# MCU.net
KiCad netlist of a schematic drawn in Altium Designer
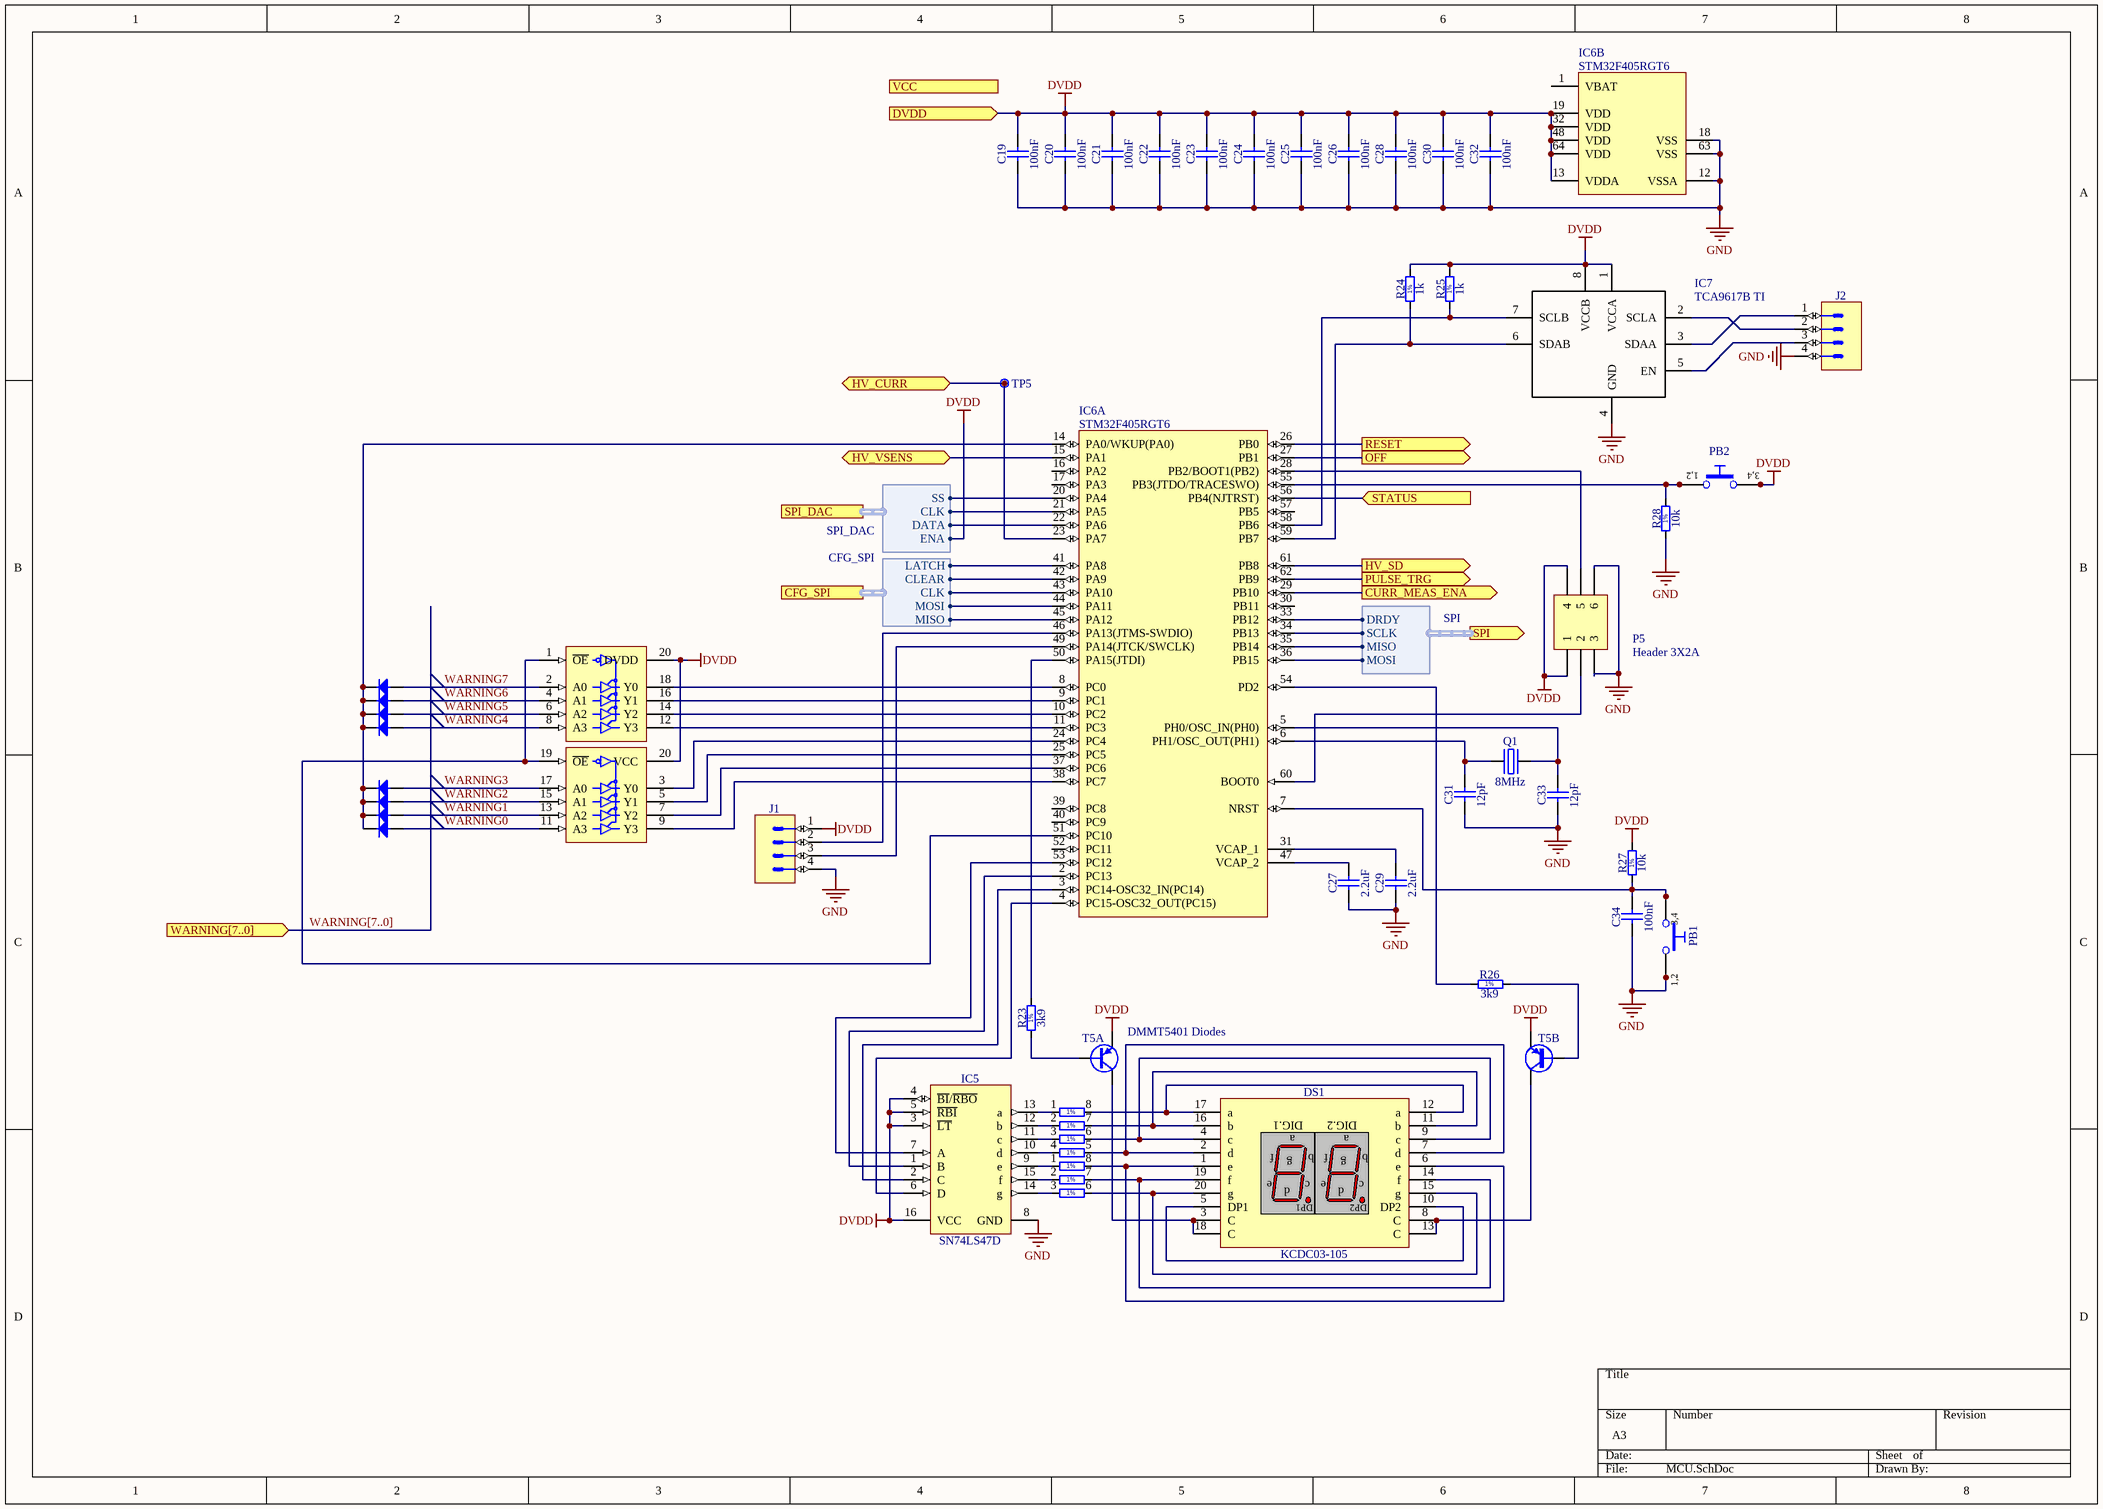
[diagram p0: MCU.SchDoc]

(export (version "E")
  (design (tool "Eeschema 10.0.6"))
  (components
    (comp (ref "C19")
      (value "100nF")
      (footprint "CAPC2012X135N")
      (description "Non-polarised capacitor")
      (fields
        (field (name "PART NUMBER") "CC0805_100NF_50V_10%_X7R")
        (field (name "VOLTAGE") "50V")
        (field (name "AUTHOR") "CERN DEM JLC")
      )
      (libsource (lib "Capacitors") (part "Capacitor - non polarized"))
    )
    (comp (ref "C20")
      (value "100nF")
      (footprint "CAPC2012X135N")
      (description "Non-polarised capacitor")
      (fields
        (field (name "PART NUMBER") "CC0805_100NF_50V_10%_X7R")
        (field (name "VOLTAGE") "50V")
        (field (name "AUTHOR") "CERN DEM JLC")
      )
      (libsource (lib "Capacitors") (part "Capacitor - non polarized"))
    )
    (comp (ref "C21")
      (value "100nF")
      (footprint "CAPC2012X135N")
      (description "Non-polarised capacitor")
      (fields
        (field (name "PART NUMBER") "CC0805_100NF_50V_10%_X7R")
        (field (name "VOLTAGE") "50V")
        (field (name "AUTHOR") "CERN DEM JLC")
      )
      (libsource (lib "Capacitors") (part "Capacitor - non polarized"))
    )
    (comp (ref "C22")
      (value "100nF")
      (footprint "CAPC2012X135N")
      (description "Non-polarised capacitor")
      (fields
        (field (name "PART NUMBER") "CC0805_100NF_50V_10%_X7R")
        (field (name "VOLTAGE") "50V")
        (field (name "AUTHOR") "CERN DEM JLC")
      )
      (libsource (lib "Capacitors") (part "Capacitor - non polarized"))
    )
    (comp (ref "C23")
      (value "100nF")
      (footprint "CAPC2012X135N")
      (description "Non-polarised capacitor")
      (fields
        (field (name "PART NUMBER") "CC0805_100NF_50V_10%_X7R")
        (field (name "VOLTAGE") "50V")
        (field (name "AUTHOR") "CERN DEM JLC")
      )
      (libsource (lib "Capacitors") (part "Capacitor - non polarized"))
    )
    (comp (ref "C24")
      (value "100nF")
      (footprint "CAPC2012X135N")
      (description "Non-polarised capacitor")
      (fields
        (field (name "PART NUMBER") "CC0805_100NF_50V_10%_X7R")
        (field (name "VOLTAGE") "50V")
        (field (name "AUTHOR") "CERN DEM JLC")
      )
      (libsource (lib "Capacitors") (part "Capacitor - non polarized"))
    )
    (comp (ref "C25")
      (value "100nF")
      (footprint "CAPC2012X135N")
      (description "Non-polarised capacitor")
      (fields
        (field (name "PART NUMBER") "CC0805_100NF_50V_10%_X7R")
        (field (name "VOLTAGE") "50V")
        (field (name "AUTHOR") "CERN DEM JLC")
      )
      (libsource (lib "Capacitors") (part "Capacitor - non polarized"))
    )
    (comp (ref "C26")
      (value "100nF")
      (footprint "CAPC2012X135N")
      (description "Non-polarised capacitor")
      (fields
        (field (name "PART NUMBER") "CC0805_100NF_50V_10%_X7R")
        (field (name "VOLTAGE") "50V")
        (field (name "AUTHOR") "CERN DEM JLC")
      )
      (libsource (lib "Capacitors") (part "Capacitor - non polarized"))
    )
    (comp (ref "C27")
      (value "2.2uF")
      (footprint "CAPC2012X135N")
      (description "Non-polarised capacitor")
      (fields
        (field (name "PART NUMBER") "CC0805_2.2UF_16V_10%_X7R")
        (field (name "VOLTAGE") "16V")
        (field (name "AUTHOR") "CERN DEM JLC")
      )
      (libsource (lib "Capacitors") (part "Capacitor - non polarized"))
    )
    (comp (ref "C28")
      (value "100nF")
      (footprint "CAPC2012X135N")
      (description "Non-polarised capacitor")
      (fields
        (field (name "PART NUMBER") "CC0805_100NF_50V_10%_X7R")
        (field (name "VOLTAGE") "50V")
        (field (name "AUTHOR") "CERN DEM JLC")
      )
      (libsource (lib "Capacitors") (part "Capacitor - non polarized"))
    )
    (comp (ref "C29")
      (value "2.2uF")
      (footprint "CAPC2012X135N")
      (description "Non-polarised capacitor")
      (fields
        (field (name "PART NUMBER") "CC0805_2.2UF_16V_10%_X7R")
        (field (name "VOLTAGE") "16V")
        (field (name "AUTHOR") "CERN DEM JLC")
      )
      (libsource (lib "Capacitors") (part "Capacitor - non polarized"))
    )
    (comp (ref "C30")
      (value "100nF")
      (footprint "CAPC2012X135N")
      (description "Non-polarised capacitor")
      (fields
        (field (name "PART NUMBER") "CC0805_100NF_50V_10%_X7R")
        (field (name "VOLTAGE") "50V")
        (field (name "AUTHOR") "CERN DEM JLC")
      )
      (libsource (lib "Capacitors") (part "Capacitor - non polarized"))
    )
    (comp (ref "C31")
      (value "12pF")
      (footprint "CAPC2012X135N")
      (description "Non-polarised capacitor")
      (fields
        (field (name "PART NUMBER") "CC0805_12PF_50V_5%_NP0")
        (field (name "VOLTAGE") "50V")
        (field (name "AUTHOR") "CERN DEM JLC")
      )
      (libsource (lib "Capacitors") (part "Capacitor - non polarized"))
    )
    (comp (ref "C32")
      (value "100nF")
      (footprint "CAPC2012X135N")
      (description "Non-polarised capacitor")
      (fields
        (field (name "PART NUMBER") "CC0805_100NF_50V_10%_X7R")
        (field (name "VOLTAGE") "50V")
        (field (name "AUTHOR") "CERN DEM JLC")
      )
      (libsource (lib "Capacitors") (part "Capacitor - non polarized"))
    )
    (comp (ref "C33")
      (value "12pF")
      (footprint "CAPC2012X135N")
      (description "Non-polarised capacitor")
      (fields
        (field (name "PART NUMBER") "CC0805_12PF_50V_5%_NP0")
        (field (name "VOLTAGE") "50V")
        (field (name "AUTHOR") "CERN DEM JLC")
      )
      (libsource (lib "Capacitors") (part "Capacitor - non polarized"))
    )
    (comp (ref "C34")
      (value "100nF")
      (footprint "CAPC2012X135N")
      (description "Non-polarised capacitor")
      (fields
        (field (name "PART NUMBER") "CC0805_100NF_50V_10%_X7R")
        (field (name "VOLTAGE") "50V")
        (field (name "AUTHOR") "CERN DEM JLC")
      )
      (libsource (lib "Capacitors") (part "Capacitor - non polarized"))
    )
    (comp (ref "D3")
      (value "MCL4148-TR3")
      (footprint "DIOMELF1911N")
      (description "Diode")
      (fields
        (field (name "VOLTAGE") "75V")
        (field (name "POWER") "200mA")
        (field (name "AUTHOR") "CERN DEM JLC")
      )
      (libsource (lib "ICs And Semiconductors") (part "Diode"))
    )
    (comp (ref "D4")
      (value "MCL4148-TR3")
      (footprint "DIOMELF1911N")
      (description "Diode")
      (fields
        (field (name "VOLTAGE") "75V")
        (field (name "POWER") "200mA")
        (field (name "AUTHOR") "CERN DEM JLC")
      )
      (libsource (lib "ICs And Semiconductors") (part "Diode"))
    )
    (comp (ref "D5")
      (value "MCL4148-TR3")
      (footprint "DIOMELF1911N")
      (description "Diode")
      (fields
        (field (name "VOLTAGE") "75V")
        (field (name "POWER") "200mA")
        (field (name "AUTHOR") "CERN DEM JLC")
      )
      (libsource (lib "ICs And Semiconductors") (part "Diode"))
    )
    (comp (ref "D6")
      (value "MCL4148-TR3")
      (footprint "DIOMELF1911N")
      (description "Diode")
      (fields
        (field (name "VOLTAGE") "75V")
        (field (name "POWER") "200mA")
        (field (name "AUTHOR") "CERN DEM JLC")
      )
      (libsource (lib "ICs And Semiconductors") (part "Diode"))
    )
    (comp (ref "D7")
      (value "MCL4148-TR3")
      (footprint "DIOMELF1911N")
      (description "Diode")
      (fields
        (field (name "VOLTAGE") "75V")
        (field (name "POWER") "200mA")
        (field (name "AUTHOR") "CERN DEM JLC")
      )
      (libsource (lib "ICs And Semiconductors") (part "Diode"))
    )
    (comp (ref "D8")
      (value "MCL4148-TR3")
      (footprint "DIOMELF1911N")
      (description "Diode")
      (fields
        (field (name "VOLTAGE") "75V")
        (field (name "POWER") "200mA")
        (field (name "AUTHOR") "CERN DEM JLC")
      )
      (libsource (lib "ICs And Semiconductors") (part "Diode"))
    )
    (comp (ref "D9")
      (value "MCL4148-TR3")
      (footprint "DIOMELF1911N")
      (description "Diode")
      (fields
        (field (name "VOLTAGE") "75V")
        (field (name "POWER") "200mA")
        (field (name "AUTHOR") "CERN DEM JLC")
      )
      (libsource (lib "ICs And Semiconductors") (part "Diode"))
    )
    (comp (ref "D10")
      (value "MCL4148-TR3")
      (footprint "DIOMELF1911N")
      (description "Diode")
      (fields
        (field (name "VOLTAGE") "75V")
        (field (name "POWER") "200mA")
        (field (name "AUTHOR") "CERN DEM JLC")
      )
      (libsource (lib "ICs And Semiconductors") (part "Diode"))
    )
    (comp (ref "DS1")
      (value "KCDC03-105")
      (footprint "DS_KINGBRIGHT_KCDC03-105")
      (description "Dual Digit, SMD 7-Segment Common Cathode Hyper Red Display")
      (fields
        (field (name "PART NUMBER") "DS_KINGBRIGHT_KCDC03-105")
        (field (name "MANUFACTURER") "KINGBRIGHT")
        (field (name "AUTHOR") "CERN DEM JLC")
      )
      (libsource (lib "ICs And Semiconductors") (part "DS_KINGBRIGHT_KCDC03-105"))
    )
    (comp (ref "IC4")
      (value "74HCT244D")
      (footprint "SOIC127P1032X265-20N")
      (description "Octal Buffer And Line Driver with 3-State Ouputs")
      (fields (field (name "MANUFACTURER") "NXP SEMICONDUCTORS") (field (name "AUTHOR") "CERN DEM JLC"))
      (libsource (lib "ICs And Semiconductors") (part "74244"))
    )
    (comp (ref "IC5")
      (value "SN74LS47D")
      (footprint "SOIC127P600X175-16N")
      (description "BCD-to-Seven-Segment Decoder/Driver")
      (fields (field (name "MANUFACTURER") "TEXAS INSTRUMENTS") (field (name "AUTHOR") "CERN DEM JMW"))
      (libsource (lib "ICs And Semiconductors") (part "7447"))
    )
    (comp (ref "IC6")
      (value "STM32F405RGT6")
      (footprint "QFP50P1200X1200X160-64N")
      (fields (field (name "MANUFACTURER") "ST MICROELECTRONICS") (field (name "AUTHOR") "CERN DEM JLC"))
      (libsource (lib "ICs And Semiconductors") (part "STM32F405RGT6"))
    )
    (comp (ref "IC7")
      (value "TCA9617B TI")
      (footprint "Additional:TSOP65P490X110-8N")
      (fields (field (name "MANUFACTURER") "TI"))
      (libsource (lib "Additional") (part "TCA9617B"))
    )
    (comp (ref "J1")
      (value "Header 4")
      (footprint "PRECI-DIP_350-V3-104-00-001101")
      (description "Connector 4 Male")
      (fields
        (field (name "PART NUMBER") "PRECI-DIP_350-V3-104-00-001101")
        (field (name "MANUFACTURER") "PRECI-DIP")
        (field (name "AUTHOR") "CERN DEM BC")
      )
      (libsource (lib "Connectors") (part "Connector 4 Male"))
    )
    (comp (ref "J2")
      (value "Header 4")
      (footprint "PRECI-DIP_350-V3-104-00-001101")
      (description "Connector 4 Male")
      (fields
        (field (name "PART NUMBER") "PRECI-DIP_350-V3-104-00-001101")
        (field (name "MANUFACTURER") "PRECI-DIP")
        (field (name "AUTHOR") "CERN DEM BC")
      )
      (libsource (lib "") (part "Connector 4 Male_1"))
    )
    (comp (ref "P5")
      (value "Header 3X2A")
      (footprint "HDR2X3_CEN")
      (description "Header, 3-Pin, Dual row")
      (fields (field (name "PUBLISHER") "Altium Limited"))
      (libsource (lib "Miscellaneous Connectors") (part "Header 3X2A"))
    )
    (comp (ref "PB1")
      (value "Push Button")
      (footprint "PB_OMRON_B3F-1000")
      (description "Push-Button Switch SPDT")
      (fields
        (field (name "PART NUMBER") "PB_OMRON_B3F-1000")
        (field (name "MANUFACTURER") "OMRON")
        (field (name "AUTHOR") "CERN DEM JMW")
      )
      (libsource (lib "Eletro-mechanical") (part "PB SPST 12NO-34NO"))
    )
    (comp (ref "PB2")
      (value "Push Button")
      (footprint "PB_OMRON_B3F-1000")
      (description "Push-Button Switch SPDT")
      (fields
        (field (name "PART NUMBER") "PB_OMRON_B3F-1000")
        (field (name "MANUFACTURER") "OMRON")
        (field (name "AUTHOR") "CERN DEM JMW")
      )
      (libsource (lib "Eletro-mechanical") (part "PB SPST 12NO-34NO"))
    )
    (comp (ref "Q1")
      (value "8MHz")
      (footprint "XTAL_TXC_7A")
      (description "Quartz Crystal")
      (fields
        (field (name "PART NUMBER") "XTAL_8MHZ_TXC_7A-8.000MAAE-T")
        (field (name "MANUFACTURER") "TXC CORPORATION")
        (field (name "AUTHOR") "CERN DEM JLC")
      )
      (libsource (lib "ICs And Semiconductors") (part "Quartz Crystal"))
    )
    (comp (ref "R23")
      (value "3k9")
      (footprint "RESC2012X60N")
      (description "Resistor - 1%")
      (fields
        (field (name "PART NUMBER") "R0805_3K9_1%_0.125W_100PPM")
        (field (name "POWER") "0.125W")
        (field (name "AUTHOR") "CERN DEM JLC")
      )
      (libsource (lib "Resistors") (part "Resistor - 1%"))
    )
    (comp (ref "R24")
      (value "1k")
      (footprint "RESC2012X60N")
      (description "Resistor - 1%")
      (fields
        (field (name "PART NUMBER") "R0805_1K_1%_0.125W_100PPM")
        (field (name "POWER") "0.125W")
        (field (name "AUTHOR") "CERN DEM JLC")
      )
      (libsource (lib "Resistors") (part "Resistor - 1%"))
    )
    (comp (ref "R25")
      (value "1k")
      (footprint "RESC2012X60N")
      (description "Resistor - 1%")
      (fields
        (field (name "PART NUMBER") "R0805_1K_1%_0.125W_100PPM")
        (field (name "POWER") "0.125W")
        (field (name "AUTHOR") "CERN DEM JLC")
      )
      (libsource (lib "Resistors") (part "Resistor - 1%"))
    )
    (comp (ref "R26")
      (value "3k9")
      (footprint "RESC2012X60N")
      (description "Resistor - 1%")
      (fields
        (field (name "PART NUMBER") "R0805_3K9_1%_0.125W_100PPM")
        (field (name "POWER") "0.125W")
        (field (name "AUTHOR") "CERN DEM JLC")
      )
      (libsource (lib "Resistors") (part "Resistor - 1%"))
    )
    (comp (ref "R27")
      (value "10k")
      (footprint "RESC2012X60N")
      (description "Resistor - 1%")
      (fields
        (field (name "PART NUMBER") "R0805_10K_1%_0.125W_100PPM")
        (field (name "POWER") "0.125W")
        (field (name "AUTHOR") "CERN DEM JLC")
      )
      (libsource (lib "Resistors") (part "Resistor - 1%"))
    )
    (comp (ref "R28")
      (value "10k")
      (footprint "RESC2012X60N")
      (description "Resistor - 1%")
      (fields
        (field (name "PART NUMBER") "R0805_10K_1%_0.125W_100PPM")
        (field (name "POWER") "0.125W")
        (field (name "AUTHOR") "CERN DEM JLC")
      )
      (libsource (lib "Resistors") (part "Resistor - 1%"))
    )
    (comp (ref "RN1")
      (value "220")
      (footprint "RN_VISHAY_CRA12E08")
      (description "DIL8 Resistor Network 4 Isolated Resistor 1%")
      (fields
        (field (name "PART NUMBER") "RN_220R_VISHAY_CRA12E083220RF")
        (field (name "POWER") "0.125W")
        (field (name "AUTHOR") "CERN DEM BC")
      )
      (libsource (lib "Resistors") (part "RN DIL8_4xR_Isolated_1%"))
    )
    (comp (ref "RN2")
      (value "220")
      (footprint "RN_VISHAY_CRA12E08")
      (description "DIL8 Resistor Network 4 Isolated Resistor 1%")
      (fields
        (field (name "PART NUMBER") "RN_220R_VISHAY_CRA12E083220RF")
        (field (name "POWER") "0.125W")
        (field (name "AUTHOR") "CERN DEM BC")
      )
      (libsource (lib "Resistors") (part "RN DIL8_4xR_Isolated_1%"))
    )
    (comp (ref "T5")
      (value "DMMT5401 Diodes")
      (footprint "SOT95P280X145-6N")
      (fields (field (name "MANUFACTURER") "Diodes"))
      (libsource (lib "") (part "DMMT5401_1"))
    )
    (comp (ref "TP5")
      (value "Test Point")
      (footprint "VERO_20-2136")
      (fields
        (field (name "PART NUMBER") "VERO_20-2136")
        (field (name "MANUFACTURER") "VERO TECHNOLOGIES")
        (field (name "MANUFACTURER PART NUMBER") "20-2136")
        (field (name "AUTHOR") "CERN DEM JLC")
      )
      (libsource (lib "Connectors") (part "Test Point"))
    )
  )
  (nets
    (net (code "4") (name "/CURR_MEAS_ENA") (class "Default")
      (node (ref "IC6") (pin "29") (pinfunction "PB10_29") (pintype "bidirectional"))
    )
    (net (code "5") (name "/HV_CURR") (class "Default")
      (node (ref "IC6") (pin "23") (pinfunction "PA7_23") (pintype "bidirectional"))
      (node (ref "TP5") (pin "1") (pinfunction "1_1") (pintype "bidirectional"))
    )
    (net (code "6") (name "/HV_SD") (class "Default")
      (node (ref "IC6") (pin "61") (pinfunction "PB8_61") (pintype "bidirectional"))
    )
    (net (code "7") (name "/HV_VSENS") (class "Default")
      (node (ref "IC6") (pin "15") (pinfunction "PA1_15") (pintype "bidirectional"))
    )
    (net (code "8") (name "/OFF") (class "Default")
      (node (ref "IC6") (pin "27") (pinfunction "PB1_27") (pintype "bidirectional"))
    )
    (net (code "9") (name "/PULSE_TRG") (class "Default")
      (node (ref "IC6") (pin "62") (pinfunction "PB9_62") (pintype "bidirectional"))
    )
    (net (code "10") (name "/RESET") (class "Default")
      (node (ref "IC6") (pin "26") (pinfunction "PB0_26") (pintype "bidirectional"))
    )
    (net (code "12") (name "/STATUS") (class "Default")
      (node (ref "IC6") (pin "56") (pinfunction "PB4(NJTRST)_56") (pintype "bidirectional"))
    )
    (net (code "14") (name "/WARNING0") (class "Default")
      (node (ref "D10") (pin "2") (pinfunction "A_2") (pintype "passive"))
      (node (ref "IC4") (pin "11") (pinfunction "A3_11") (pintype "input"))
    )
    (net (code "15") (name "/WARNING1") (class "Default")
      (node (ref "D9") (pin "2") (pinfunction "A_2") (pintype "passive"))
      (node (ref "IC4") (pin "13") (pinfunction "A2_13") (pintype "input"))
    )
    (net (code "16") (name "/WARNING2") (class "Default")
      (node (ref "D8") (pin "2") (pinfunction "A_2") (pintype "passive"))
      (node (ref "IC4") (pin "15") (pinfunction "A1_15") (pintype "input"))
    )
    (net (code "17") (name "/WARNING3") (class "Default")
      (node (ref "D7") (pin "2") (pinfunction "A_2") (pintype "passive"))
      (node (ref "IC4") (pin "17") (pinfunction "A0_17") (pintype "input"))
    )
    (net (code "18") (name "/WARNING4") (class "Default")
      (node (ref "D6") (pin "2") (pinfunction "A_2") (pintype "passive"))
      (node (ref "IC4") (pin "8") (pinfunction "A3_8") (pintype "input"))
    )
    (net (code "19") (name "/WARNING5") (class "Default")
      (node (ref "D5") (pin "2") (pinfunction "A_2") (pintype "passive"))
      (node (ref "IC4") (pin "6") (pinfunction "A2_6") (pintype "input"))
    )
    (net (code "20") (name "/WARNING6") (class "Default")
      (node (ref "D4") (pin "2") (pinfunction "A_2") (pintype "passive"))
      (node (ref "IC4") (pin "4") (pinfunction "A1_4") (pintype "input"))
    )
    (net (code "21") (name "/WARNING7") (class "Default")
      (node (ref "D3") (pin "2") (pinfunction "A_2") (pintype "passive"))
      (node (ref "IC4") (pin "2") (pinfunction "A0_2") (pintype "input"))
    )
    (net (code "25") (name "DVDD") (class "Default")
      (node (ref "C19") (pin "2") (pinfunction "2_2") (pintype "passive"))
      (node (ref "C20") (pin "2") (pinfunction "2_2") (pintype "passive"))
      (node (ref "C21") (pin "2") (pinfunction "2_2") (pintype "passive"))
      (node (ref "C22") (pin "2") (pinfunction "2_2") (pintype "passive"))
      (node (ref "C23") (pin "2") (pinfunction "2_2") (pintype "passive"))
      (node (ref "C24") (pin "2") (pinfunction "2_2") (pintype "passive"))
      (node (ref "C25") (pin "2") (pinfunction "2_2") (pintype "passive"))
      (node (ref "C26") (pin "2") (pinfunction "2_2") (pintype "passive"))
      (node (ref "C28") (pin "2") (pinfunction "2_2") (pintype "passive"))
      (node (ref "C30") (pin "2") (pinfunction "2_2") (pintype "passive"))
      (node (ref "C32") (pin "2") (pinfunction "2_2") (pintype "passive"))
      (node (ref "IC4") (pin "20") (pinfunction "VCC_20") (pintype "power_in"))
      (node (ref "IC5") (pin "16") (pinfunction "VCC_16") (pintype "power_in"))
      (node (ref "IC5") (pin "3") (pinfunction "~{LT}_3") (pintype "input"))
      (node (ref "IC5") (pin "4") (pinfunction "~{BI}/~{RBO}_4") (pintype "bidirectional"))
      (node (ref "IC5") (pin "5") (pinfunction "~{RBI}_5") (pintype "input"))
      (node (ref "IC6") (pin "13") (pinfunction "VDDA_13") (pintype "power_in"))
      (node (ref "IC6") (pin "19") (pinfunction "VDD_19") (pintype "power_in"))
      (node (ref "IC6") (pin "32") (pinfunction "VDD_32") (pintype "power_in"))
      (node (ref "IC6") (pin "48") (pinfunction "VDD_48") (pintype "power_in"))
      (node (ref "IC6") (pin "64") (pinfunction "VDD_64") (pintype "power_in"))
      (node (ref "IC7") (pin "1") (pinfunction "VCCA_1") (pintype "passive"))
      (node (ref "IC7") (pin "8") (pinfunction "VCCB_8") (pintype "passive"))
      (node (ref "J1") (pin "1") (pinfunction "1_1") (pintype "bidirectional"))
      (node (ref "P5") (pin "1") (pinfunction "1_1") (pintype "passive"))
      (node (ref "P5") (pin "4") (pinfunction "4_4") (pintype "passive"))
      (node (ref "PB2") (pin "3") (pinfunction "3_3") (pintype "passive"))
      (node (ref "PB2") (pin "4") (pinfunction "4_4") (pintype "passive"))
      (node (ref "R24") (pin "2") (pinfunction "2_2") (pintype "passive"))
      (node (ref "R25") (pin "2") (pinfunction "2_2") (pintype "passive"))
      (node (ref "R27") (pin "2") (pinfunction "2_2") (pintype "passive"))
      (node (ref "T5") (pin "5") (pinfunction "E_5") (pintype "passive"))
      (node (ref "T5") (pin "6") (pinfunction "E_6") (pintype "passive"))
    )
    (net (code "26") (name "GND") (class "Default")
      (node (ref "C19") (pin "1") (pinfunction "1_1") (pintype "passive"))
      (node (ref "C20") (pin "1") (pinfunction "1_1") (pintype "passive"))
      (node (ref "C21") (pin "1") (pinfunction "1_1") (pintype "passive"))
      (node (ref "C22") (pin "1") (pinfunction "1_1") (pintype "passive"))
      (node (ref "C23") (pin "1") (pinfunction "1_1") (pintype "passive"))
      (node (ref "C24") (pin "1") (pinfunction "1_1") (pintype "passive"))
      (node (ref "C25") (pin "1") (pinfunction "1_1") (pintype "passive"))
      (node (ref "C26") (pin "1") (pinfunction "1_1") (pintype "passive"))
      (node (ref "C27") (pin "1") (pinfunction "1_1") (pintype "passive"))
      (node (ref "C28") (pin "1") (pinfunction "1_1") (pintype "passive"))
      (node (ref "C29") (pin "1") (pinfunction "1_1") (pintype "passive"))
      (node (ref "C30") (pin "1") (pinfunction "1_1") (pintype "passive"))
      (node (ref "C31") (pin "1") (pinfunction "1_1") (pintype "passive"))
      (node (ref "C32") (pin "1") (pinfunction "1_1") (pintype "passive"))
      (node (ref "C33") (pin "1") (pinfunction "1_1") (pintype "passive"))
      (node (ref "C34") (pin "1") (pinfunction "1_1") (pintype "passive"))
      (node (ref "IC4") (pin "10") (pinfunction "GND_10") (pintype "power_in"))
      (node (ref "IC5") (pin "8") (pinfunction "GND_8") (pintype "power_in"))
      (node (ref "IC6") (pin "12") (pinfunction "VSSA_12") (pintype "power_in"))
      (node (ref "IC6") (pin "18") (pinfunction "VSS_18") (pintype "power_in"))
      (node (ref "IC6") (pin "63") (pinfunction "VSS_63") (pintype "power_in"))
      (node (ref "IC7") (pin "4") (pinfunction "GND_4") (pintype "passive"))
      (node (ref "J1") (pin "4") (pinfunction "4_4") (pintype "bidirectional"))
      (node (ref "J2") (pin "4") (pinfunction "4_4") (pintype "bidirectional"))
      (node (ref "P5") (pin "3") (pinfunction "3_3") (pintype "passive"))
      (node (ref "P5") (pin "6") (pinfunction "6_6") (pintype "passive"))
      (node (ref "PB1") (pin "1") (pinfunction "1_1") (pintype "passive"))
      (node (ref "PB1") (pin "2") (pinfunction "2_2") (pintype "passive"))
      (node (ref "R28") (pin "1") (pinfunction "1_1") (pintype "passive"))
    )
    (net (code "27") (name "Net-(D10-C)") (class "Default")
      (node (ref "D10") (pin "1") (pinfunction "C_1") (pintype "passive"))
      (node (ref "D3") (pin "1") (pinfunction "C_1") (pintype "passive"))
      (node (ref "D4") (pin "1") (pinfunction "C_1") (pintype "passive"))
      (node (ref "D5") (pin "1") (pinfunction "C_1") (pintype "passive"))
      (node (ref "D6") (pin "1") (pinfunction "C_1") (pintype "passive"))
      (node (ref "D7") (pin "1") (pinfunction "C_1") (pintype "passive"))
      (node (ref "D8") (pin "1") (pinfunction "C_1") (pintype "passive"))
      (node (ref "D9") (pin "1") (pinfunction "C_1") (pintype "passive"))
      (node (ref "IC6") (pin "14") (pinfunction "PA0/WKUP(PA0)_14") (pintype "bidirectional"))
    )
    (net (code "28") (name "Net-(DS1-DP1)") (class "Default")
      (node (ref "DS1") (pin "10") (pinfunction "DP2_10") (pintype "passive"))
      (node (ref "DS1") (pin "5") (pinfunction "DP1_5") (pintype "passive"))
    )
    (net (code "29") (name "Net-(DS1-a-Pad12)") (class "Default")
      (node (ref "DS1") (pin "12") (pinfunction "a_12") (pintype "passive"))
      (node (ref "DS1") (pin "17") (pinfunction "a_17") (pintype "passive"))
      (node (ref "RN1") (pin "8") (pinfunction "8_8") (pintype "passive"))
    )
    (net (code "30") (name "Net-(DS1-b-Pad11)") (class "Default")
      (node (ref "DS1") (pin "11") (pinfunction "b_11") (pintype "passive"))
      (node (ref "DS1") (pin "16") (pinfunction "b_16") (pintype "passive"))
      (node (ref "RN1") (pin "7") (pinfunction "7_7") (pintype "passive"))
    )
    (net (code "31") (name "Net-(DS1-c-Pad4)") (class "Default")
      (node (ref "DS1") (pin "4") (pinfunction "c_4") (pintype "passive"))
      (node (ref "DS1") (pin "9") (pinfunction "c_9") (pintype "passive"))
      (node (ref "RN1") (pin "6") (pinfunction "6_6") (pintype "passive"))
    )
    (net (code "32") (name "Net-(DS1-d-Pad2)") (class "Default")
      (node (ref "DS1") (pin "2") (pinfunction "d_2") (pintype "passive"))
      (node (ref "DS1") (pin "7") (pinfunction "d_7") (pintype "passive"))
      (node (ref "RN1") (pin "5") (pinfunction "5_5") (pintype "passive"))
    )
    (net (code "33") (name "Net-(DS1-e-Pad1)") (class "Default")
      (node (ref "DS1") (pin "1") (pinfunction "e_1") (pintype "passive"))
      (node (ref "DS1") (pin "6") (pinfunction "e_6") (pintype "passive"))
      (node (ref "RN2") (pin "8") (pinfunction "8_8") (pintype "passive"))
    )
    (net (code "34") (name "Net-(DS1-f-Pad14)") (class "Default")
      (node (ref "DS1") (pin "14") (pinfunction "f_14") (pintype "passive"))
      (node (ref "DS1") (pin "19") (pinfunction "f_19") (pintype "passive"))
      (node (ref "RN2") (pin "7") (pinfunction "7_7") (pintype "passive"))
    )
    (net (code "35") (name "Net-(DS1-g-Pad15)") (class "Default")
      (node (ref "DS1") (pin "15") (pinfunction "g_15") (pintype "passive"))
      (node (ref "DS1") (pin "20") (pinfunction "g_20") (pintype "passive"))
      (node (ref "RN2") (pin "6") (pinfunction "6_6") (pintype "passive"))
    )
    (net (code "36") (name "Net-(IC4A-Y0)") (class "Default")
      (node (ref "IC4") (pin "18") (pinfunction "Y0_18") (pintype "tri_state"))
      (node (ref "IC6") (pin "8") (pinfunction "PC0_8") (pintype "bidirectional"))
    )
    (net (code "37") (name "Net-(IC4A-Y1)") (class "Default")
      (node (ref "IC4") (pin "16") (pinfunction "Y1_16") (pintype "tri_state"))
      (node (ref "IC6") (pin "9") (pinfunction "PC1_9") (pintype "bidirectional"))
    )
    (net (code "38") (name "Net-(IC4A-Y2)") (class "Default")
      (node (ref "IC4") (pin "14") (pinfunction "Y2_14") (pintype "tri_state"))
      (node (ref "IC6") (pin "10") (pinfunction "PC2_10") (pintype "bidirectional"))
    )
    (net (code "39") (name "Net-(IC4A-Y3)") (class "Default")
      (node (ref "IC4") (pin "12") (pinfunction "Y3_12") (pintype "tri_state"))
      (node (ref "IC6") (pin "11") (pinfunction "PC3_11") (pintype "bidirectional"))
    )
    (net (code "40") (name "Net-(IC4A-~{OE})") (class "Default")
      (node (ref "IC4") (pin "1") (pinfunction "~{OE}_1") (pintype "input"))
      (node (ref "IC4") (pin "19") (pinfunction "~{OE}_19") (pintype "input"))
      (node (ref "IC6") (pin "51") (pinfunction "PC10_51") (pintype "bidirectional"))
    )
    (net (code "41") (name "Net-(IC4B-Y0)") (class "Default")
      (node (ref "IC4") (pin "3") (pinfunction "Y0_3") (pintype "tri_state"))
      (node (ref "IC6") (pin "24") (pinfunction "PC4_24") (pintype "bidirectional"))
    )
    (net (code "42") (name "Net-(IC4B-Y1)") (class "Default")
      (node (ref "IC4") (pin "5") (pinfunction "Y1_5") (pintype "tri_state"))
      (node (ref "IC6") (pin "25") (pinfunction "PC5_25") (pintype "bidirectional"))
    )
    (net (code "43") (name "Net-(IC4B-Y2)") (class "Default")
      (node (ref "IC4") (pin "7") (pinfunction "Y2_7") (pintype "tri_state"))
      (node (ref "IC6") (pin "37") (pinfunction "PC6_37") (pintype "bidirectional"))
    )
    (net (code "44") (name "Net-(IC4B-Y3)") (class "Default")
      (node (ref "IC4") (pin "9") (pinfunction "Y3_9") (pintype "tri_state"))
      (node (ref "IC6") (pin "38") (pinfunction "PC7_38") (pintype "bidirectional"))
    )
    (net (code "45") (name "Net-(IC5-A)") (class "Default")
      (node (ref "IC5") (pin "7") (pinfunction "A_7") (pintype "input"))
      (node (ref "IC6") (pin "53") (pinfunction "PC12_53") (pintype "bidirectional"))
    )
    (net (code "46") (name "Net-(IC5-B)") (class "Default")
      (node (ref "IC5") (pin "1") (pinfunction "B_1") (pintype "input"))
      (node (ref "IC6") (pin "2") (pinfunction "PC13_2") (pintype "bidirectional"))
    )
    (net (code "47") (name "Net-(IC5-C)") (class "Default")
      (node (ref "IC5") (pin "2") (pinfunction "C_2") (pintype "input"))
      (node (ref "IC6") (pin "3") (pinfunction "PC14-OSC32_IN(PC14)_3") (pintype "bidirectional"))
    )
    (net (code "48") (name "Net-(IC5-D)") (class "Default")
      (node (ref "IC5") (pin "6") (pinfunction "D_6") (pintype "input"))
      (node (ref "IC6") (pin "4") (pinfunction "PC15-OSC32_OUT(PC15)_4") (pintype "bidirectional"))
    )
    (net (code "49") (name "Net-(IC5-a)") (class "Default")
      (node (ref "IC5") (pin "13") (pinfunction "a_13") (pintype "output"))
      (node (ref "RN1") (pin "1") (pinfunction "1_1") (pintype "passive"))
    )
    (net (code "50") (name "Net-(IC5-b)") (class "Default")
      (node (ref "IC5") (pin "12") (pinfunction "b_12") (pintype "output"))
      (node (ref "RN1") (pin "2") (pinfunction "2_2") (pintype "passive"))
    )
    (net (code "51") (name "Net-(IC5-c)") (class "Default")
      (node (ref "IC5") (pin "11") (pinfunction "c_11") (pintype "output"))
      (node (ref "RN1") (pin "3") (pinfunction "3_3") (pintype "passive"))
    )
    (net (code "52") (name "Net-(IC5-d)") (class "Default")
      (node (ref "IC5") (pin "10") (pinfunction "d_10") (pintype "output"))
      (node (ref "RN1") (pin "4") (pinfunction "4_4") (pintype "passive"))
    )
    (net (code "53") (name "Net-(IC5-e)") (class "Default")
      (node (ref "IC5") (pin "9") (pinfunction "e_9") (pintype "output"))
      (node (ref "RN2") (pin "1") (pinfunction "1_1") (pintype "passive"))
    )
    (net (code "54") (name "Net-(IC5-f)") (class "Default")
      (node (ref "IC5") (pin "15") (pinfunction "f_15") (pintype "output"))
      (node (ref "RN2") (pin "2") (pinfunction "2_2") (pintype "passive"))
    )
    (net (code "55") (name "Net-(IC5-g)") (class "Default")
      (node (ref "IC5") (pin "14") (pinfunction "g_14") (pintype "output"))
      (node (ref "RN2") (pin "3") (pinfunction "3_3") (pintype "passive"))
    )
    (net (code "56") (name "Net-(IC6A-BOOT0)") (class "Default")
      (node (ref "IC6") (pin "60") (pinfunction "BOOT0_60") (pintype "input"))
      (node (ref "P5") (pin "2") (pinfunction "2_2") (pintype "passive"))
    )
    (net (code "57") (name "Net-(IC6A-NRST)") (class "Default")
      (node (ref "C34") (pin "2") (pinfunction "2_2") (pintype "passive"))
      (node (ref "IC6") (pin "7") (pinfunction "NRST_7") (pintype "bidirectional"))
      (node (ref "PB1") (pin "3") (pinfunction "3_3") (pintype "passive"))
      (node (ref "PB1") (pin "4") (pinfunction "4_4") (pintype "passive"))
      (node (ref "R27") (pin "1") (pinfunction "1_1") (pintype "passive"))
    )
    (net (code "58") (name "Net-(IC6A-PA13(JTMS-SWDIO))") (class "Default")
      (node (ref "IC6") (pin "46") (pinfunction "PA13(JTMS-SWDIO)_46") (pintype "bidirectional"))
      (node (ref "J1") (pin "2") (pinfunction "2_2") (pintype "bidirectional"))
    )
    (net (code "59") (name "Net-(IC6A-PA14(JTCK{slash}SWCLK))") (class "Default")
      (node (ref "IC6") (pin "49") (pinfunction "PA14(JTCK/SWCLK)_49") (pintype "bidirectional"))
      (node (ref "J1") (pin "3") (pinfunction "3_3") (pintype "bidirectional"))
    )
    (net (code "60") (name "Net-(IC6A-PA15(JTDI))") (class "Default")
      (node (ref "IC6") (pin "50") (pinfunction "PA15(JTDI)_50") (pintype "bidirectional"))
      (node (ref "R23") (pin "2") (pinfunction "2_2") (pintype "passive"))
    )
    (net (code "61") (name "Net-(IC6A-PB2{slash}BOOT1(PB2))") (class "Default")
      (node (ref "IC6") (pin "28") (pinfunction "PB2/BOOT1(PB2)_28") (pintype "bidirectional"))
      (node (ref "P5") (pin "5") (pinfunction "5_5") (pintype "passive"))
    )
    (net (code "62") (name "Net-(IC6A-PB3(JTDO{slash}TRACESWO))") (class "Default")
      (node (ref "IC6") (pin "55") (pinfunction "PB3(JTDO/TRACESWO)_55") (pintype "bidirectional"))
      (node (ref "PB2") (pin "1") (pinfunction "1_1") (pintype "passive"))
      (node (ref "PB2") (pin "2") (pinfunction "2_2") (pintype "passive"))
      (node (ref "R28") (pin "2") (pinfunction "2_2") (pintype "passive"))
    )
    (net (code "63") (name "Net-(IC6A-PB6)") (class "Default")
      (node (ref "IC6") (pin "58") (pinfunction "PB6_58") (pintype "bidirectional"))
      (node (ref "IC7") (pin "7") (pinfunction "SCLB_7") (pintype "passive"))
      (node (ref "R25") (pin "1") (pinfunction "1_1") (pintype "passive"))
    )
    (net (code "64") (name "Net-(IC6A-PB7)") (class "Default")
      (node (ref "IC6") (pin "59") (pinfunction "PB7_59") (pintype "bidirectional"))
      (node (ref "IC7") (pin "6") (pinfunction "SDAB_6") (pintype "passive"))
      (node (ref "R24") (pin "1") (pinfunction "1_1") (pintype "passive"))
    )
    (net (code "65") (name "Net-(IC6A-PD2)") (class "Default")
      (node (ref "IC6") (pin "54") (pinfunction "PD2_54") (pintype "bidirectional"))
      (node (ref "R26") (pin "1") (pinfunction "1_1") (pintype "passive"))
    )
    (net (code "66") (name "Net-(IC6A-PH0{slash}OSC_IN(PH0))") (class "Default")
      (node (ref "C33") (pin "2") (pinfunction "2_2") (pintype "passive"))
      (node (ref "IC6") (pin "5") (pinfunction "PH0/OSC_IN(PH0)_5") (pintype "bidirectional"))
      (node (ref "Q1") (pin "2") (pinfunction "OSC2_2") (pintype "passive"))
    )
    (net (code "67") (name "Net-(IC6A-PH1{slash}OSC_OUT(PH1))") (class "Default")
      (node (ref "C31") (pin "2") (pinfunction "2_2") (pintype "passive"))
      (node (ref "IC6") (pin "6") (pinfunction "PH1/OSC_OUT(PH1)_6") (pintype "bidirectional"))
      (node (ref "Q1") (pin "1") (pinfunction "OSC1_1") (pintype "passive"))
    )
    (net (code "68") (name "Net-(IC6A-VCAP_1)") (class "Default")
      (node (ref "C29") (pin "2") (pinfunction "2_2") (pintype "passive"))
      (node (ref "IC6") (pin "31") (pinfunction "VCAP_1_31") (pintype "power_in"))
    )
    (net (code "69") (name "Net-(IC6A-VCAP_2)") (class "Default")
      (node (ref "C27") (pin "2") (pinfunction "2_2") (pintype "passive"))
      (node (ref "IC6") (pin "47") (pinfunction "VCAP_2_47") (pintype "power_in"))
    )
    (net (code "70") (name "Net-(IC7-EN)") (class "Default")
      (node (ref "IC7") (pin "5") (pinfunction "EN_5") (pintype "passive"))
      (node (ref "J2") (pin "3") (pinfunction "3_3") (pintype "bidirectional"))
    )
    (net (code "71") (name "Net-(IC7-SCLA)") (class "Default")
      (node (ref "IC7") (pin "2") (pinfunction "SCLA_2") (pintype "passive"))
      (node (ref "J2") (pin "2") (pinfunction "2_2") (pintype "bidirectional"))
    )
    (net (code "72") (name "Net-(IC7-SDAA)") (class "Default")
      (node (ref "IC7") (pin "3") (pinfunction "SDAA_3") (pintype "passive"))
      (node (ref "J2") (pin "1") (pinfunction "1_1") (pintype "bidirectional"))
    )
    (net (code "73") (name "Net-(T5A-B)") (class "Default")
      (node (ref "R23") (pin "1") (pinfunction "1_1") (pintype "passive"))
      (node (ref "T5") (pin "2") (pinfunction "B_2") (pintype "passive"))
    )
    (net (code "74") (name "Net-(T5A-C)") (class "Default")
      (node (ref "DS1") (pin "18") (pinfunction "C_18") (pintype "passive"))
      (node (ref "DS1") (pin "3") (pinfunction "C_3") (pintype "passive"))
      (node (ref "T5") (pin "1") (pinfunction "C_1") (pintype "passive"))
    )
    (net (code "75") (name "Net-(T5B-B)") (class "Default")
      (node (ref "R26") (pin "2") (pinfunction "2_2") (pintype "passive"))
      (node (ref "T5") (pin "3") (pinfunction "B_3") (pintype "passive"))
    )
    (net (code "76") (name "Net-(T5B-C)") (class "Default")
      (node (ref "DS1") (pin "13") (pinfunction "C_13") (pintype "passive"))
      (node (ref "DS1") (pin "8") (pinfunction "C_8") (pintype "passive"))
      (node (ref "T5") (pin "4") (pinfunction "C_4") (pintype "passive"))
    )
    (net (code "77") (name "unconnected-(IC6A-PA2-Pad16)") (class "Default")
      (node (ref "IC6") (pin "16") (pinfunction "PA2_16") (pintype "bidirectional"))
    )
    (net (code "78") (name "unconnected-(IC6A-PA3-Pad17)") (class "Default")
      (node (ref "IC6") (pin "17") (pinfunction "PA3_17") (pintype "bidirectional"))
    )
    (net (code "79") (name "unconnected-(IC6A-PA4-Pad20)") (class "Default")
      (node (ref "IC6") (pin "20") (pinfunction "PA4_20") (pintype "bidirectional"))
    )
    (net (code "80") (name "unconnected-(IC6A-PA5-Pad21)") (class "Default")
      (node (ref "IC6") (pin "21") (pinfunction "PA5_21") (pintype "bidirectional"))
    )
    (net (code "81") (name "unconnected-(IC6A-PA6-Pad22)") (class "Default")
      (node (ref "IC6") (pin "22") (pinfunction "PA6_22") (pintype "bidirectional"))
    )
    (net (code "82") (name "unconnected-(IC6A-PA8-Pad41)") (class "Default")
      (node (ref "IC6") (pin "41") (pinfunction "PA8_41") (pintype "bidirectional"))
    )
    (net (code "83") (name "unconnected-(IC6A-PA9-Pad42)") (class "Default")
      (node (ref "IC6") (pin "42") (pinfunction "PA9_42") (pintype "bidirectional"))
    )
    (net (code "84") (name "unconnected-(IC6A-PA10-Pad43)") (class "Default")
      (node (ref "IC6") (pin "43") (pinfunction "PA10_43") (pintype "bidirectional"))
    )
    (net (code "85") (name "unconnected-(IC6A-PA11-Pad44)") (class "Default")
      (node (ref "IC6") (pin "44") (pinfunction "PA11_44") (pintype "bidirectional"))
    )
    (net (code "86") (name "unconnected-(IC6A-PA12-Pad45)") (class "Default")
      (node (ref "IC6") (pin "45") (pinfunction "PA12_45") (pintype "bidirectional"))
    )
    (net (code "87") (name "unconnected-(IC6A-PB5-Pad57)") (class "Default")
      (node (ref "IC6") (pin "57") (pinfunction "PB5_57") (pintype "bidirectional"))
    )
    (net (code "88") (name "unconnected-(IC6A-PB11-Pad30)") (class "Default")
      (node (ref "IC6") (pin "30") (pinfunction "PB11_30") (pintype "bidirectional"))
    )
    (net (code "89") (name "unconnected-(IC6A-PB12-Pad33)") (class "Default")
      (node (ref "IC6") (pin "33") (pinfunction "PB12_33") (pintype "bidirectional"))
    )
    (net (code "90") (name "unconnected-(IC6A-PB13-Pad34)") (class "Default")
      (node (ref "IC6") (pin "34") (pinfunction "PB13_34") (pintype "bidirectional"))
    )
    (net (code "91") (name "unconnected-(IC6A-PB14-Pad35)") (class "Default")
      (node (ref "IC6") (pin "35") (pinfunction "PB14_35") (pintype "bidirectional"))
    )
    (net (code "92") (name "unconnected-(IC6A-PB15-Pad36)") (class "Default")
      (node (ref "IC6") (pin "36") (pinfunction "PB15_36") (pintype "bidirectional"))
    )
    (net (code "93") (name "unconnected-(IC6A-PC8-Pad39)") (class "Default")
      (node (ref "IC6") (pin "39") (pinfunction "PC8_39") (pintype "bidirectional"))
    )
    (net (code "94") (name "unconnected-(IC6A-PC9-Pad40)") (class "Default")
      (node (ref "IC6") (pin "40") (pinfunction "PC9_40") (pintype "bidirectional"))
    )
    (net (code "95") (name "unconnected-(IC6A-PC11-Pad52)") (class "Default")
      (node (ref "IC6") (pin "52") (pinfunction "PC11_52") (pintype "bidirectional"))
    )
    (net (code "96") (name "unconnected-(IC6B-VBAT-Pad1)") (class "Default")
      (node (ref "IC6") (pin "1") (pinfunction "VBAT_1") (pintype "power_in"))
    )
  )
)
